# LED_Matrix.net
KiCad netlist of a schematic drawn in Altium Designer
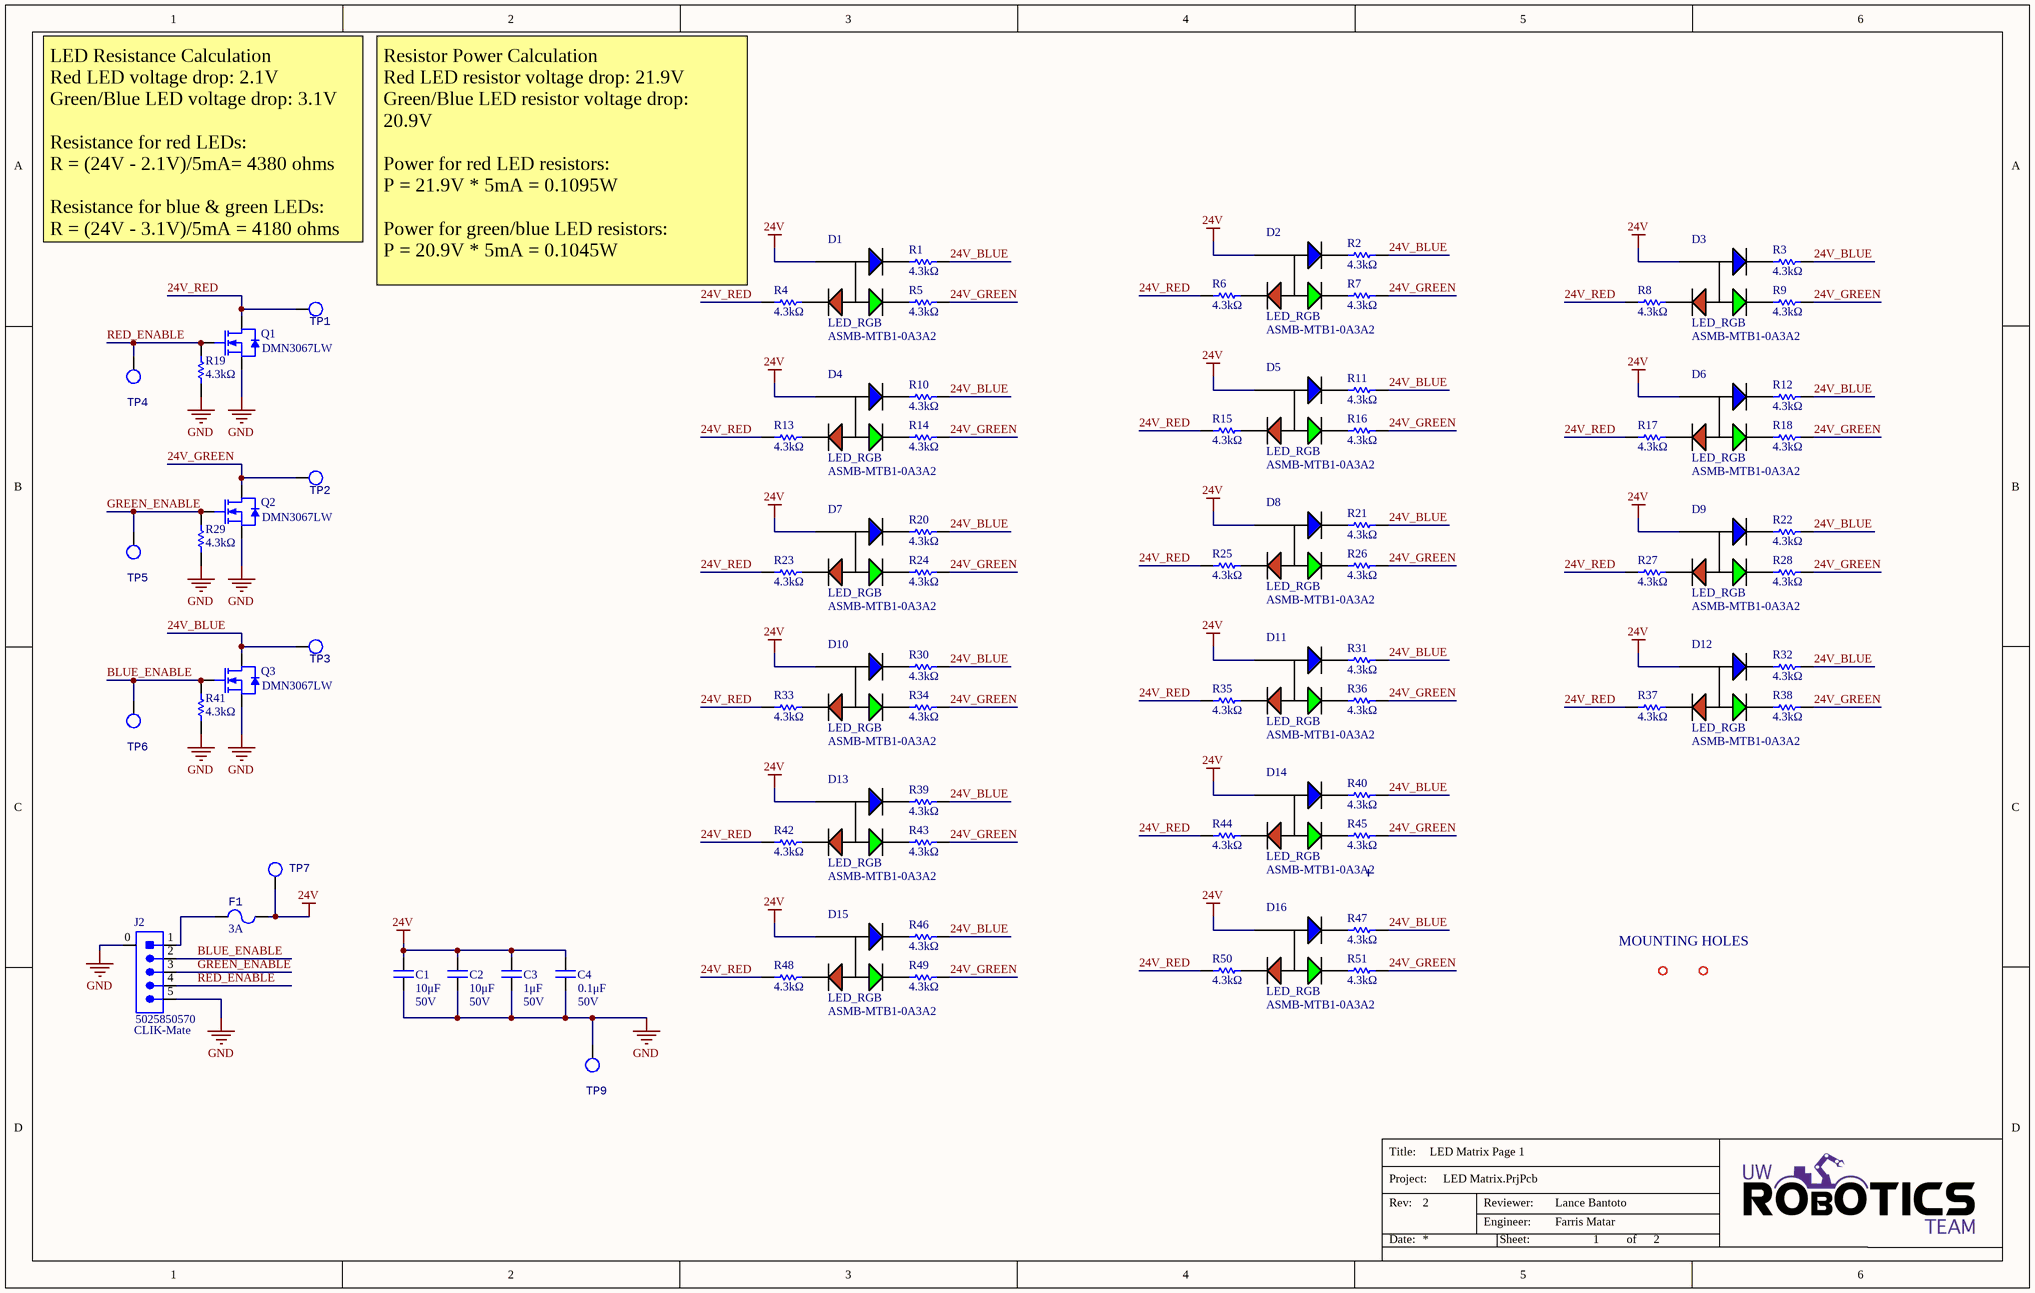
[diagram p0: LED Matrix.SchDoc]

(export (version "E")
  (design (tool "Eeschema 10.0.6"))
  (components
    (comp (ref "C1")
      (value "10μF")
      (footprint "CAP1210")
      (description "CAP CER 10UF 50V X7R 1210")
      (fields (field (name "VOLTAGE RATING") "50V") (field (name "Comment") "CAP_10uF_50V_1210"))
      (libsource (lib "UWRT_Schematic_Library_2020") (part "CAP_10uF_50V_1210"))
    )
    (comp (ref "C2")
      (value "10μF")
      (footprint "CAP1210")
      (description "CAP CER 10UF 50V X7R 1210")
      (fields (field (name "VOLTAGE RATING") "50V") (field (name "Comment") "CAP_10uF_50V_1210"))
      (libsource (lib "UWRT_Schematic_Library_2020") (part "CAP_10uF_50V_1210"))
    )
    (comp (ref "C3")
      (value "1μF")
      (footprint "CAP2012")
      (description "CAP CER 1UF 50V X7R 0805")
      (fields
        (field (name "VOLTAGE RATING") "50V")
        (field (name "LCSC PART #") "C28323")
        (field (name "Comment") "CAP_1uF_50V_0805")
      )
      (libsource (lib "UWRT_Schematic_Library_2020") (part "CAP_1uF_50V_0805"))
    )
    (comp (ref "C4")
      (value "0.1μF")
      (footprint "CAP2012")
      (description "CAP CER 0.1UF 50V X7R 0805")
      (fields
        (field (name "LCSC PART #") "C49678")
        (field (name "VOLTAGE RATING") "50V")
        (field (name "Comment") "CAP_0.1uF_50V_0805")
      )
      (libsource (lib "UWRT_Schematic_Library_2020") (part "CAP_0.1uF_50V_0805"))
    )
    (comp (ref "D1")
      (value "LED_RGB")
      (footprint "LED_RGB")
      (description "LED RGB DIFFUSED 4PLCC SMD")
      (fields (field (name "MANUFACTURER PART NUMBER 1") "ASMB-MTB1-0A3A2"))
      (libsource (lib "UWRT_Schematic_Library_2020") (part "LED_RGB"))
    )
    (comp (ref "D2")
      (value "LED_RGB")
      (footprint "LED_RGB")
      (description "LED RGB DIFFUSED 4PLCC SMD")
      (fields (field (name "MANUFACTURER PART NUMBER 1") "ASMB-MTB1-0A3A2"))
      (libsource (lib "UWRT_Schematic_Library_2020") (part "LED_RGB"))
    )
    (comp (ref "D3")
      (value "LED_RGB")
      (footprint "LED_RGB")
      (description "LED RGB DIFFUSED 4PLCC SMD")
      (fields (field (name "MANUFACTURER PART NUMBER 1") "ASMB-MTB1-0A3A2"))
      (libsource (lib "UWRT_Schematic_Library_2020") (part "LED_RGB"))
    )
    (comp (ref "D4")
      (value "LED_RGB")
      (footprint "LED_RGB")
      (description "LED RGB DIFFUSED 4PLCC SMD")
      (fields (field (name "MANUFACTURER PART NUMBER 1") "ASMB-MTB1-0A3A2"))
      (libsource (lib "UWRT_Schematic_Library_2020") (part "LED_RGB"))
    )
    (comp (ref "D5")
      (value "LED_RGB")
      (footprint "LED_RGB")
      (description "LED RGB DIFFUSED 4PLCC SMD")
      (fields (field (name "MANUFACTURER PART NUMBER 1") "ASMB-MTB1-0A3A2"))
      (libsource (lib "UWRT_Schematic_Library_2020") (part "LED_RGB"))
    )
    (comp (ref "D6")
      (value "LED_RGB")
      (footprint "LED_RGB")
      (description "LED RGB DIFFUSED 4PLCC SMD")
      (fields (field (name "MANUFACTURER PART NUMBER 1") "ASMB-MTB1-0A3A2"))
      (libsource (lib "UWRT_Schematic_Library_2020") (part "LED_RGB"))
    )
    (comp (ref "D7")
      (value "LED_RGB")
      (footprint "LED_RGB")
      (description "LED RGB DIFFUSED 4PLCC SMD")
      (fields (field (name "MANUFACTURER PART NUMBER 1") "ASMB-MTB1-0A3A2"))
      (libsource (lib "UWRT_Schematic_Library_2020") (part "LED_RGB"))
    )
    (comp (ref "D8")
      (value "LED_RGB")
      (footprint "LED_RGB")
      (description "LED RGB DIFFUSED 4PLCC SMD")
      (fields (field (name "MANUFACTURER PART NUMBER 1") "ASMB-MTB1-0A3A2"))
      (libsource (lib "UWRT_Schematic_Library_2020") (part "LED_RGB"))
    )
    (comp (ref "D9")
      (value "LED_RGB")
      (footprint "LED_RGB")
      (description "LED RGB DIFFUSED 4PLCC SMD")
      (fields (field (name "MANUFACTURER PART NUMBER 1") "ASMB-MTB1-0A3A2"))
      (libsource (lib "UWRT_Schematic_Library_2020") (part "LED_RGB"))
    )
    (comp (ref "D10")
      (value "LED_RGB")
      (footprint "LED_RGB")
      (description "LED RGB DIFFUSED 4PLCC SMD")
      (fields (field (name "MANUFACTURER PART NUMBER 1") "ASMB-MTB1-0A3A2"))
      (libsource (lib "UWRT_Schematic_Library_2020") (part "LED_RGB"))
    )
    (comp (ref "D11")
      (value "LED_RGB")
      (footprint "LED_RGB")
      (description "LED RGB DIFFUSED 4PLCC SMD")
      (fields (field (name "MANUFACTURER PART NUMBER 1") "ASMB-MTB1-0A3A2"))
      (libsource (lib "UWRT_Schematic_Library_2020") (part "LED_RGB"))
    )
    (comp (ref "D12")
      (value "LED_RGB")
      (footprint "LED_RGB")
      (description "LED RGB DIFFUSED 4PLCC SMD")
      (fields (field (name "MANUFACTURER PART NUMBER 1") "ASMB-MTB1-0A3A2"))
      (libsource (lib "UWRT_Schematic_Library_2020") (part "LED_RGB"))
    )
    (comp (ref "D13")
      (value "LED_RGB")
      (footprint "LED_RGB")
      (description "LED RGB DIFFUSED 4PLCC SMD")
      (fields (field (name "MANUFACTURER PART NUMBER 1") "ASMB-MTB1-0A3A2"))
      (libsource (lib "UWRT_Schematic_Library_2020") (part "LED_RGB"))
    )
    (comp (ref "D14")
      (value "LED_RGB")
      (footprint "LED_RGB")
      (description "LED RGB DIFFUSED 4PLCC SMD")
      (fields (field (name "MANUFACTURER PART NUMBER 1") "ASMB-MTB1-0A3A2"))
      (libsource (lib "UWRT_Schematic_Library_2020") (part "LED_RGB"))
    )
    (comp (ref "D15")
      (value "LED_RGB")
      (footprint "LED_RGB")
      (description "LED RGB DIFFUSED 4PLCC SMD")
      (fields (field (name "MANUFACTURER PART NUMBER 1") "ASMB-MTB1-0A3A2"))
      (libsource (lib "UWRT_Schematic_Library_2020") (part "LED_RGB"))
    )
    (comp (ref "D16")
      (value "LED_RGB")
      (footprint "LED_RGB")
      (description "LED RGB DIFFUSED 4PLCC SMD")
      (fields (field (name "MANUFACTURER PART NUMBER 1") "ASMB-MTB1-0A3A2"))
      (libsource (lib "UWRT_Schematic_Library_2020") (part "LED_RGB"))
    )
    (comp (ref "F1")
      (value "FUSE_3A_1206")
      (footprint "FUSE_1206")
      (description "FUSE BOARD MNT 3A 32VAC/VDC 1206")
      (fields (field (name "CURRENT RATING") "3A"))
      (libsource (lib "UWRT_Schematic_Library_2020") (part "FUSE_3A_1206"))
    )
    (comp (ref "J2")
      (value "CON_5M_SM_RA")
      (footprint "MOLEX-5025850570")
      (description "CONN HEADER SMD RIGHT ANGLE 1.5MM PITCH")
      (fields (field (name "MANUFACTURER PART NUMBER 1") "5025850570") (field (name "FAMILY") "CLIK-Mate"))
      (libsource (lib "UWRT_Schematic_Library_2020") (part "CON_5M_SM_RA"))
    )
    (comp (ref "MH1")
      (value "MOUNTING_HOLES")
      (footprint "MOUNTING_HOLE")
      (description "6cm x 6cm")
      (libsource (lib "UWRT_Schematic_Library_2020") (part "MOUNTING_HOLES"))
    )
    (comp (ref "MH2")
      (value "MOUNTING_HOLES")
      (footprint "MOUNTING_HOLE")
      (description "6cm x 6cm")
      (libsource (lib "UWRT_Schematic_Library_2020") (part "MOUNTING_HOLES"))
    )
    (comp (ref "Q1")
      (value "NMOS_30V_2.6A")
      (footprint "NMOS_SOT-323")
      (description "MOSFET N-CH 30V 2.6A SOT-323")
      (fields (field (name "MANUFACTURER PART NUMBER 1") "DMN3067LW"))
      (libsource (lib "UWRT_Schematic_Library_2020") (part "NMOS_30V_2.6A"))
    )
    (comp (ref "Q2")
      (value "NMOS_30V_2.6A")
      (footprint "NMOS_SOT-323")
      (description "MOSFET N-CH 30V 2.6A SOT-323")
      (fields (field (name "MANUFACTURER PART NUMBER 1") "DMN3067LW"))
      (libsource (lib "UWRT_Schematic_Library_2020") (part "NMOS_30V_2.6A"))
    )
    (comp (ref "Q3")
      (value "NMOS_30V_2.6A")
      (footprint "NMOS_SOT-323")
      (description "MOSFET N-CH 30V 2.6A SOT-323")
      (fields (field (name "MANUFACTURER PART NUMBER 1") "DMN3067LW"))
      (libsource (lib "UWRT_Schematic_Library_2020") (part "NMOS_30V_2.6A"))
    )
    (comp (ref "R1")
      (value "RES_4.3kΩ_1210_5%")
      (footprint "RES1210")
      (description "RES 4.3K OHM 5% 1/2W 1210")
      (fields (field (name "RESISTANCE") "4.3kΩ") (field (name "TOLERANCE") "5%"))
      (libsource (lib "UWRT_Schematic_Library_2020") (part "RES_4.3kΩ_1210_5%"))
    )
    (comp (ref "R2")
      (value "RES_4.3kΩ_1210_5%")
      (footprint "RES1210")
      (description "RES 4.3K OHM 5% 1/2W 1210")
      (fields (field (name "RESISTANCE") "4.3kΩ") (field (name "TOLERANCE") "5%"))
      (libsource (lib "UWRT_Schematic_Library_2020") (part "RES_4.3kΩ_1210_5%"))
    )
    (comp (ref "R3")
      (value "RES_4.3kΩ_1210_5%")
      (footprint "RES1210")
      (description "RES 4.3K OHM 5% 1/2W 1210")
      (fields (field (name "RESISTANCE") "4.3kΩ") (field (name "TOLERANCE") "5%"))
      (libsource (lib "UWRT_Schematic_Library_2020") (part "RES_4.3kΩ_1210_5%"))
    )
    (comp (ref "R4")
      (value "RES_4.3kΩ_1210_5%")
      (footprint "RES1210")
      (description "RES 4.3K OHM 5% 1/2W 1210")
      (fields (field (name "RESISTANCE") "4.3kΩ") (field (name "TOLERANCE") "5%"))
      (libsource (lib "UWRT_Schematic_Library_2020") (part "RES_4.3kΩ_1210_5%"))
    )
    (comp (ref "R5")
      (value "RES_4.3kΩ_1210_5%")
      (footprint "RES1210")
      (description "RES 4.3K OHM 5% 1/2W 1210")
      (fields (field (name "RESISTANCE") "4.3kΩ") (field (name "TOLERANCE") "5%"))
      (libsource (lib "UWRT_Schematic_Library_2020") (part "RES_4.3kΩ_1210_5%"))
    )
    (comp (ref "R6")
      (value "RES_4.3kΩ_1210_5%")
      (footprint "RES1210")
      (description "RES 4.3K OHM 5% 1/2W 1210")
      (fields (field (name "RESISTANCE") "4.3kΩ") (field (name "TOLERANCE") "5%"))
      (libsource (lib "UWRT_Schematic_Library_2020") (part "RES_4.3kΩ_1210_5%"))
    )
    (comp (ref "R7")
      (value "RES_4.3kΩ_1210_5%")
      (footprint "RES1210")
      (description "RES 4.3K OHM 5% 1/2W 1210")
      (fields (field (name "RESISTANCE") "4.3kΩ") (field (name "TOLERANCE") "5%"))
      (libsource (lib "UWRT_Schematic_Library_2020") (part "RES_4.3kΩ_1210_5%"))
    )
    (comp (ref "R8")
      (value "RES_4.3kΩ_1210_5%")
      (footprint "RES1210")
      (description "RES 4.3K OHM 5% 1/2W 1210")
      (fields (field (name "RESISTANCE") "4.3kΩ") (field (name "TOLERANCE") "5%"))
      (libsource (lib "UWRT_Schematic_Library_2020") (part "RES_4.3kΩ_1210_5%"))
    )
    (comp (ref "R9")
      (value "RES_4.3kΩ_1210_5%")
      (footprint "RES1210")
      (description "RES 4.3K OHM 5% 1/2W 1210")
      (fields (field (name "RESISTANCE") "4.3kΩ") (field (name "TOLERANCE") "5%"))
      (libsource (lib "UWRT_Schematic_Library_2020") (part "RES_4.3kΩ_1210_5%"))
    )
    (comp (ref "R10")
      (value "RES_4.3kΩ_1210_5%")
      (footprint "RES1210")
      (description "RES 4.3K OHM 5% 1/2W 1210")
      (fields (field (name "RESISTANCE") "4.3kΩ") (field (name "TOLERANCE") "5%"))
      (libsource (lib "UWRT_Schematic_Library_2020") (part "RES_4.3kΩ_1210_5%"))
    )
    (comp (ref "R11")
      (value "RES_4.3kΩ_1210_5%")
      (footprint "RES1210")
      (description "RES 4.3K OHM 5% 1/2W 1210")
      (fields (field (name "RESISTANCE") "4.3kΩ") (field (name "TOLERANCE") "5%"))
      (libsource (lib "UWRT_Schematic_Library_2020") (part "RES_4.3kΩ_1210_5%"))
    )
    (comp (ref "R12")
      (value "RES_4.3kΩ_1210_5%")
      (footprint "RES1210")
      (description "RES 4.3K OHM 5% 1/2W 1210")
      (fields (field (name "RESISTANCE") "4.3kΩ") (field (name "TOLERANCE") "5%"))
      (libsource (lib "UWRT_Schematic_Library_2020") (part "RES_4.3kΩ_1210_5%"))
    )
    (comp (ref "R13")
      (value "RES_4.3kΩ_1210_5%")
      (footprint "RES1210")
      (description "RES 4.3K OHM 5% 1/2W 1210")
      (fields (field (name "RESISTANCE") "4.3kΩ") (field (name "TOLERANCE") "5%"))
      (libsource (lib "UWRT_Schematic_Library_2020") (part "RES_4.3kΩ_1210_5%"))
    )
    (comp (ref "R14")
      (value "RES_4.3kΩ_1210_5%")
      (footprint "RES1210")
      (description "RES 4.3K OHM 5% 1/2W 1210")
      (fields (field (name "RESISTANCE") "4.3kΩ") (field (name "TOLERANCE") "5%"))
      (libsource (lib "UWRT_Schematic_Library_2020") (part "RES_4.3kΩ_1210_5%"))
    )
    (comp (ref "R15")
      (value "RES_4.3kΩ_1210_5%")
      (footprint "RES1210")
      (description "RES 4.3K OHM 5% 1/2W 1210")
      (fields (field (name "RESISTANCE") "4.3kΩ") (field (name "TOLERANCE") "5%"))
      (libsource (lib "UWRT_Schematic_Library_2020") (part "RES_4.3kΩ_1210_5%"))
    )
    (comp (ref "R16")
      (value "RES_4.3kΩ_1210_5%")
      (footprint "RES1210")
      (description "RES 4.3K OHM 5% 1/2W 1210")
      (fields (field (name "RESISTANCE") "4.3kΩ") (field (name "TOLERANCE") "5%"))
      (libsource (lib "UWRT_Schematic_Library_2020") (part "RES_4.3kΩ_1210_5%"))
    )
    (comp (ref "R17")
      (value "RES_4.3kΩ_1210_5%")
      (footprint "RES1210")
      (description "RES 4.3K OHM 5% 1/2W 1210")
      (fields (field (name "RESISTANCE") "4.3kΩ") (field (name "TOLERANCE") "5%"))
      (libsource (lib "UWRT_Schematic_Library_2020") (part "RES_4.3kΩ_1210_5%"))
    )
    (comp (ref "R18")
      (value "RES_4.3kΩ_1210_5%")
      (footprint "RES1210")
      (description "RES 4.3K OHM 5% 1/2W 1210")
      (fields (field (name "RESISTANCE") "4.3kΩ") (field (name "TOLERANCE") "5%"))
      (libsource (lib "UWRT_Schematic_Library_2020") (part "RES_4.3kΩ_1210_5%"))
    )
    (comp (ref "R19")
      (value "RES_4.3kΩ_1210_5%")
      (footprint "RES1210")
      (description "RES 4.3K OHM 5% 1/2W 1210")
      (fields (field (name "RESISTANCE") "4.3kΩ") (field (name "TOLERANCE") "5%"))
      (libsource (lib "UWRT_Schematic_Library_2020") (part "RES_4.3kΩ_1210_5%"))
    )
    (comp (ref "R20")
      (value "RES_4.3kΩ_1210_5%")
      (footprint "RES1210")
      (description "RES 4.3K OHM 5% 1/2W 1210")
      (fields (field (name "RESISTANCE") "4.3kΩ") (field (name "TOLERANCE") "5%"))
      (libsource (lib "UWRT_Schematic_Library_2020") (part "RES_4.3kΩ_1210_5%"))
    )
    (comp (ref "R21")
      (value "RES_4.3kΩ_1210_5%")
      (footprint "RES1210")
      (description "RES 4.3K OHM 5% 1/2W 1210")
      (fields (field (name "RESISTANCE") "4.3kΩ") (field (name "TOLERANCE") "5%"))
      (libsource (lib "UWRT_Schematic_Library_2020") (part "RES_4.3kΩ_1210_5%"))
    )
    (comp (ref "R22")
      (value "RES_4.3kΩ_1210_5%")
      (footprint "RES1210")
      (description "RES 4.3K OHM 5% 1/2W 1210")
      (fields (field (name "RESISTANCE") "4.3kΩ") (field (name "TOLERANCE") "5%"))
      (libsource (lib "UWRT_Schematic_Library_2020") (part "RES_4.3kΩ_1210_5%"))
    )
    (comp (ref "R23")
      (value "RES_4.3kΩ_1210_5%")
      (footprint "RES1210")
      (description "RES 4.3K OHM 5% 1/2W 1210")
      (fields (field (name "RESISTANCE") "4.3kΩ") (field (name "TOLERANCE") "5%"))
      (libsource (lib "UWRT_Schematic_Library_2020") (part "RES_4.3kΩ_1210_5%"))
    )
    (comp (ref "R24")
      (value "RES_4.3kΩ_1210_5%")
      (footprint "RES1210")
      (description "RES 4.3K OHM 5% 1/2W 1210")
      (fields (field (name "RESISTANCE") "4.3kΩ") (field (name "TOLERANCE") "5%"))
      (libsource (lib "UWRT_Schematic_Library_2020") (part "RES_4.3kΩ_1210_5%"))
    )
    (comp (ref "R25")
      (value "RES_4.3kΩ_1210_5%")
      (footprint "RES1210")
      (description "RES 4.3K OHM 5% 1/2W 1210")
      (fields (field (name "RESISTANCE") "4.3kΩ") (field (name "TOLERANCE") "5%"))
      (libsource (lib "UWRT_Schematic_Library_2020") (part "RES_4.3kΩ_1210_5%"))
    )
    (comp (ref "R26")
      (value "RES_4.3kΩ_1210_5%")
      (footprint "RES1210")
      (description "RES 4.3K OHM 5% 1/2W 1210")
      (fields (field (name "RESISTANCE") "4.3kΩ") (field (name "TOLERANCE") "5%"))
      (libsource (lib "UWRT_Schematic_Library_2020") (part "RES_4.3kΩ_1210_5%"))
    )
    (comp (ref "R27")
      (value "RES_4.3kΩ_1210_5%")
      (footprint "RES1210")
      (description "RES 4.3K OHM 5% 1/2W 1210")
      (fields (field (name "RESISTANCE") "4.3kΩ") (field (name "TOLERANCE") "5%"))
      (libsource (lib "UWRT_Schematic_Library_2020") (part "RES_4.3kΩ_1210_5%"))
    )
    (comp (ref "R28")
      (value "RES_4.3kΩ_1210_5%")
      (footprint "RES1210")
      (description "RES 4.3K OHM 5% 1/2W 1210")
      (fields (field (name "RESISTANCE") "4.3kΩ") (field (name "TOLERANCE") "5%"))
      (libsource (lib "UWRT_Schematic_Library_2020") (part "RES_4.3kΩ_1210_5%"))
    )
    (comp (ref "R29")
      (value "RES_4.3kΩ_1210_5%")
      (footprint "RES1210")
      (description "RES 4.3K OHM 5% 1/2W 1210")
      (fields (field (name "RESISTANCE") "4.3kΩ") (field (name "TOLERANCE") "5%"))
      (libsource (lib "UWRT_Schematic_Library_2020") (part "RES_4.3kΩ_1210_5%"))
    )
    (comp (ref "R30")
      (value "RES_4.3kΩ_1210_5%")
      (footprint "RES1210")
      (description "RES 4.3K OHM 5% 1/2W 1210")
      (fields (field (name "RESISTANCE") "4.3kΩ") (field (name "TOLERANCE") "5%"))
      (libsource (lib "UWRT_Schematic_Library_2020") (part "RES_4.3kΩ_1210_5%"))
    )
    (comp (ref "R31")
      (value "RES_4.3kΩ_1210_5%")
      (footprint "RES1210")
      (description "RES 4.3K OHM 5% 1/2W 1210")
      (fields (field (name "RESISTANCE") "4.3kΩ") (field (name "TOLERANCE") "5%"))
      (libsource (lib "UWRT_Schematic_Library_2020") (part "RES_4.3kΩ_1210_5%"))
    )
    (comp (ref "R32")
      (value "RES_4.3kΩ_1210_5%")
      (footprint "RES1210")
      (description "RES 4.3K OHM 5% 1/2W 1210")
      (fields (field (name "RESISTANCE") "4.3kΩ") (field (name "TOLERANCE") "5%"))
      (libsource (lib "UWRT_Schematic_Library_2020") (part "RES_4.3kΩ_1210_5%"))
    )
    (comp (ref "R33")
      (value "RES_4.3kΩ_1210_5%")
      (footprint "RES1210")
      (description "RES 4.3K OHM 5% 1/2W 1210")
      (fields (field (name "RESISTANCE") "4.3kΩ") (field (name "TOLERANCE") "5%"))
      (libsource (lib "UWRT_Schematic_Library_2020") (part "RES_4.3kΩ_1210_5%"))
    )
    (comp (ref "R34")
      (value "RES_4.3kΩ_1210_5%")
      (footprint "RES1210")
      (description "RES 4.3K OHM 5% 1/2W 1210")
      (fields (field (name "RESISTANCE") "4.3kΩ") (field (name "TOLERANCE") "5%"))
      (libsource (lib "UWRT_Schematic_Library_2020") (part "RES_4.3kΩ_1210_5%"))
    )
    (comp (ref "R35")
      (value "RES_4.3kΩ_1210_5%")
      (footprint "RES1210")
      (description "RES 4.3K OHM 5% 1/2W 1210")
      (fields (field (name "RESISTANCE") "4.3kΩ") (field (name "TOLERANCE") "5%"))
      (libsource (lib "UWRT_Schematic_Library_2020") (part "RES_4.3kΩ_1210_5%"))
    )
    (comp (ref "R36")
      (value "RES_4.3kΩ_1210_5%")
      (footprint "RES1210")
      (description "RES 4.3K OHM 5% 1/2W 1210")
      (fields (field (name "RESISTANCE") "4.3kΩ") (field (name "TOLERANCE") "5%"))
      (libsource (lib "UWRT_Schematic_Library_2020") (part "RES_4.3kΩ_1210_5%"))
    )
    (comp (ref "R37")
      (value "RES_4.3kΩ_1210_5%")
      (footprint "RES1210")
      (description "RES 4.3K OHM 5% 1/2W 1210")
      (fields (field (name "RESISTANCE") "4.3kΩ") (field (name "TOLERANCE") "5%"))
      (libsource (lib "UWRT_Schematic_Library_2020") (part "RES_4.3kΩ_1210_5%"))
    )
    (comp (ref "R38")
      (value "RES_4.3kΩ_1210_5%")
      (footprint "RES1210")
      (description "RES 4.3K OHM 5% 1/2W 1210")
      (fields (field (name "RESISTANCE") "4.3kΩ") (field (name "TOLERANCE") "5%"))
      (libsource (lib "UWRT_Schematic_Library_2020") (part "RES_4.3kΩ_1210_5%"))
    )
    (comp (ref "R39")
      (value "RES_4.3kΩ_1210_5%")
      (footprint "RES1210")
      (description "RES 4.3K OHM 5% 1/2W 1210")
      (fields (field (name "RESISTANCE") "4.3kΩ") (field (name "TOLERANCE") "5%"))
      (libsource (lib "UWRT_Schematic_Library_2020") (part "RES_4.3kΩ_1210_5%"))
    )
    (comp (ref "R40")
      (value "RES_4.3kΩ_1210_5%")
      (footprint "RES1210")
      (description "RES 4.3K OHM 5% 1/2W 1210")
      (fields (field (name "RESISTANCE") "4.3kΩ") (field (name "TOLERANCE") "5%"))
      (libsource (lib "UWRT_Schematic_Library_2020") (part "RES_4.3kΩ_1210_5%"))
    )
    (comp (ref "R41")
      (value "RES_4.3kΩ_1210_5%")
      (footprint "RES1210")
      (description "RES 4.3K OHM 5% 1/2W 1210")
      (fields (field (name "RESISTANCE") "4.3kΩ") (field (name "TOLERANCE") "5%"))
      (libsource (lib "UWRT_Schematic_Library_2020") (part "RES_4.3kΩ_1210_5%"))
    )
    (comp (ref "R42")
      (value "RES_4.3kΩ_1210_5%")
      (footprint "RES1210")
      (description "RES 4.3K OHM 5% 1/2W 1210")
      (fields (field (name "RESISTANCE") "4.3kΩ") (field (name "TOLERANCE") "5%"))
      (libsource (lib "UWRT_Schematic_Library_2020") (part "RES_4.3kΩ_1210_5%"))
    )
    (comp (ref "R43")
      (value "RES_4.3kΩ_1210_5%")
      (footprint "RES1210")
      (description "RES 4.3K OHM 5% 1/2W 1210")
      (fields (field (name "RESISTANCE") "4.3kΩ") (field (name "TOLERANCE") "5%"))
      (libsource (lib "UWRT_Schematic_Library_2020") (part "RES_4.3kΩ_1210_5%"))
    )
    (comp (ref "R44")
      (value "RES_4.3kΩ_1210_5%")
      (footprint "RES1210")
      (description "RES 4.3K OHM 5% 1/2W 1210")
      (fields (field (name "RESISTANCE") "4.3kΩ") (field (name "TOLERANCE") "5%"))
      (libsource (lib "UWRT_Schematic_Library_2020") (part "RES_4.3kΩ_1210_5%"))
    )
    (comp (ref "R45")
      (value "RES_4.3kΩ_1210_5%")
      (footprint "RES1210")
      (description "RES 4.3K OHM 5% 1/2W 1210")
      (fields (field (name "RESISTANCE") "4.3kΩ") (field (name "TOLERANCE") "5%"))
      (libsource (lib "UWRT_Schematic_Library_2020") (part "RES_4.3kΩ_1210_5%"))
    )
    (comp (ref "R46")
      (value "RES_4.3kΩ_1210_5%")
      (footprint "RES1210")
      (description "RES 4.3K OHM 5% 1/2W 1210")
      (fields (field (name "RESISTANCE") "4.3kΩ") (field (name "TOLERANCE") "5%"))
      (libsource (lib "UWRT_Schematic_Library_2020") (part "RES_4.3kΩ_1210_5%"))
    )
    (comp (ref "R47")
      (value "RES_4.3kΩ_1210_5%")
      (footprint "RES1210")
      (description "RES 4.3K OHM 5% 1/2W 1210")
      (fields (field (name "RESISTANCE") "4.3kΩ") (field (name "TOLERANCE") "5%"))
      (libsource (lib "UWRT_Schematic_Library_2020") (part "RES_4.3kΩ_1210_5%"))
    )
    (comp (ref "R48")
      (value "RES_4.3kΩ_1210_5%")
      (footprint "RES1210")
      (description "RES 4.3K OHM 5% 1/2W 1210")
      (fields (field (name "RESISTANCE") "4.3kΩ") (field (name "TOLERANCE") "5%"))
      (libsource (lib "UWRT_Schematic_Library_2020") (part "RES_4.3kΩ_1210_5%"))
    )
    (comp (ref "R49")
      (value "RES_4.3kΩ_1210_5%")
      (footprint "RES1210")
      (description "RES 4.3K OHM 5% 1/2W 1210")
      (fields (field (name "RESISTANCE") "4.3kΩ") (field (name "TOLERANCE") "5%"))
      (libsource (lib "UWRT_Schematic_Library_2020") (part "RES_4.3kΩ_1210_5%"))
    )
    (comp (ref "R50")
      (value "RES_4.3kΩ_1210_5%")
      (footprint "RES1210")
      (description "RES 4.3K OHM 5% 1/2W 1210")
      (fields (field (name "RESISTANCE") "4.3kΩ") (field (name "TOLERANCE") "5%"))
      (libsource (lib "UWRT_Schematic_Library_2020") (part "RES_4.3kΩ_1210_5%"))
    )
    (comp (ref "R51")
      (value "RES_4.3kΩ_1210_5%")
      (footprint "RES1210")
      (description "RES 4.3K OHM 5% 1/2W 1210")
      (fields (field (name "RESISTANCE") "4.3kΩ") (field (name "TOLERANCE") "5%"))
      (libsource (lib "UWRT_Schematic_Library_2020") (part "RES_4.3kΩ_1210_5%"))
    )
    (comp (ref "TP1")
      (value "TESTPOINT_LOOP")
      (footprint "TESTPOINT_LOOP")
      (description "TESTPOINT THRUHOLE")
      (libsource (lib "UWRT_Schematic_Library_2020") (part "TESTPOINT_LOOP"))
    )
    (comp (ref "TP2")
      (value "TESTPOINT_LOOP")
      (footprint "TESTPOINT_LOOP")
      (description "TESTPOINT THRUHOLE")
      (libsource (lib "UWRT_Schematic_Library_2020") (part "TESTPOINT_LOOP"))
    )
    (comp (ref "TP3")
      (value "TESTPOINT_LOOP")
      (footprint "TESTPOINT_LOOP")
      (description "TESTPOINT THRUHOLE")
      (libsource (lib "UWRT_Schematic_Library_2020") (part "TESTPOINT_LOOP"))
    )
    (comp (ref "TP4")
      (value "TESTPOINT_LOOP")
      (footprint "TESTPOINT_LOOP")
      (description "TESTPOINT THRUHOLE")
      (libsource (lib "UWRT_Schematic_Library_2020") (part "TESTPOINT_LOOP"))
    )
    (comp (ref "TP5")
      (value "TESTPOINT_LOOP")
      (footprint "TESTPOINT_LOOP")
      (description "TESTPOINT THRUHOLE")
      (libsource (lib "UWRT_Schematic_Library_2020") (part "TESTPOINT_LOOP"))
    )
    (comp (ref "TP6")
      (value "TESTPOINT_LOOP")
      (footprint "TESTPOINT_LOOP")
      (description "TESTPOINT THRUHOLE")
      (libsource (lib "UWRT_Schematic_Library_2020") (part "TESTPOINT_LOOP"))
    )
    (comp (ref "TP7")
      (value "TESTPOINT_LOOP")
      (footprint "TESTPOINT_LOOP")
      (description "TESTPOINT THRUHOLE")
      (libsource (lib "UWRT_Schematic_Library_2020") (part "TESTPOINT_LOOP"))
    )
    (comp (ref "TP9")
      (value "TESTPOINT_LOOP")
      (footprint "TESTPOINT_LOOP")
      (description "TESTPOINT THRUHOLE")
      (libsource (lib "UWRT_Schematic_Library_2020") (part "TESTPOINT_LOOP"))
    )
  )
  (nets
    (net (code "1") (name "/24V_BLUE") (class "Default")
      (node (ref "Q3") (pin "3") (pinfunction "DRAIN_3") (pintype "passive"))
      (node (ref "R1") (pin "2") (pinfunction "2_2") (pintype "passive"))
      (node (ref "R10") (pin "2") (pinfunction "2_2") (pintype "passive"))
      (node (ref "R11") (pin "2") (pinfunction "2_2") (pintype "passive"))
      (node (ref "R12") (pin "2") (pinfunction "2_2") (pintype "passive"))
      (node (ref "R2") (pin "2") (pinfunction "2_2") (pintype "passive"))
      (node (ref "R20") (pin "1") (pinfunction "1_1") (pintype "passive"))
      (node (ref "R21") (pin "1") (pinfunction "1_1") (pintype "passive"))
      (node (ref "R22") (pin "1") (pinfunction "1_1") (pintype "passive"))
      (node (ref "R3") (pin "2") (pinfunction "2_2") (pintype "passive"))
      (node (ref "R30") (pin "2") (pinfunction "2_2") (pintype "passive"))
      (node (ref "R31") (pin "2") (pinfunction "2_2") (pintype "passive"))
      (node (ref "R32") (pin "2") (pinfunction "2_2") (pintype "passive"))
      (node (ref "R39") (pin "1") (pinfunction "1_1") (pintype "passive"))
      (node (ref "R40") (pin "2") (pinfunction "2_2") (pintype "passive"))
      (node (ref "R46") (pin "2") (pinfunction "2_2") (pintype "passive"))
      (node (ref "R47") (pin "2") (pinfunction "2_2") (pintype "passive"))
      (node (ref "TP3") (pin "1") (pintype "passive"))
    )
    (net (code "2") (name "/24V_GREEN") (class "Default")
      (node (ref "Q2") (pin "3") (pinfunction "DRAIN_3") (pintype "passive"))
      (node (ref "R14") (pin "2") (pinfunction "2_2") (pintype "passive"))
      (node (ref "R16") (pin "2") (pinfunction "2_2") (pintype "passive"))
      (node (ref "R18") (pin "2") (pinfunction "2_2") (pintype "passive"))
      (node (ref "R24") (pin "2") (pinfunction "2_2") (pintype "passive"))
      (node (ref "R26") (pin "2") (pinfunction "2_2") (pintype "passive"))
      (node (ref "R28") (pin "2") (pinfunction "2_2") (pintype "passive"))
      (node (ref "R34") (pin "2") (pinfunction "2_2") (pintype "passive"))
      (node (ref "R36") (pin "2") (pinfunction "2_2") (pintype "passive"))
      (node (ref "R38") (pin "2") (pinfunction "2_2") (pintype "passive"))
      (node (ref "R43") (pin "2") (pinfunction "2_2") (pintype "passive"))
      (node (ref "R45") (pin "2") (pinfunction "2_2") (pintype "passive"))
      (node (ref "R49") (pin "2") (pinfunction "2_2") (pintype "passive"))
      (node (ref "R5") (pin "2") (pinfunction "2_2") (pintype "passive"))
      (node (ref "R51") (pin "2") (pinfunction "2_2") (pintype "passive"))
      (node (ref "R7") (pin "2") (pinfunction "2_2") (pintype "passive"))
      (node (ref "R9") (pin "2") (pinfunction "2_2") (pintype "passive"))
      (node (ref "TP2") (pin "1") (pintype "passive"))
    )
    (net (code "3") (name "/24V_RED") (class "Default")
      (node (ref "Q1") (pin "3") (pinfunction "DRAIN_3") (pintype "passive"))
      (node (ref "R13") (pin "1") (pinfunction "1_1") (pintype "passive"))
      (node (ref "R15") (pin "1") (pinfunction "1_1") (pintype "passive"))
      (node (ref "R17") (pin "1") (pinfunction "1_1") (pintype "passive"))
      (node (ref "R23") (pin "2") (pinfunction "2_2") (pintype "passive"))
      (node (ref "R25") (pin "1") (pinfunction "1_1") (pintype "passive"))
      (node (ref "R27") (pin "1") (pinfunction "1_1") (pintype "passive"))
      (node (ref "R33") (pin "1") (pinfunction "1_1") (pintype "passive"))
      (node (ref "R35") (pin "1") (pinfunction "1_1") (pintype "passive"))
      (node (ref "R37") (pin "1") (pinfunction "1_1") (pintype "passive"))
      (node (ref "R4") (pin "1") (pinfunction "1_1") (pintype "passive"))
      (node (ref "R42") (pin "1") (pinfunction "1_1") (pintype "passive"))
      (node (ref "R44") (pin "1") (pinfunction "1_1") (pintype "passive"))
      (node (ref "R48") (pin "1") (pinfunction "1_1") (pintype "passive"))
      (node (ref "R50") (pin "1") (pinfunction "1_1") (pintype "passive"))
      (node (ref "R6") (pin "1") (pinfunction "1_1") (pintype "passive"))
      (node (ref "R8") (pin "1") (pinfunction "1_1") (pintype "passive"))
      (node (ref "TP1") (pin "1") (pintype "passive"))
    )
    (net (code "4") (name "/BLUE_ENABLE") (class "Default")
      (node (ref "J2") (pin "2") (pinfunction "2_2") (pintype "passive"))
      (node (ref "Q3") (pin "1") (pinfunction "GATE_1") (pintype "passive"))
      (node (ref "R41") (pin "2") (pinfunction "2_2") (pintype "passive"))
      (node (ref "TP6") (pin "1") (pintype "passive"))
    )
    (net (code "5") (name "/GREEN_ENABLE") (class "Default")
      (node (ref "J2") (pin "3") (pinfunction "3_3") (pintype "passive"))
      (node (ref "Q2") (pin "1") (pinfunction "GATE_1") (pintype "passive"))
      (node (ref "R29") (pin "2") (pinfunction "2_2") (pintype "passive"))
      (node (ref "TP5") (pin "1") (pintype "passive"))
    )
    (net (code "6") (name "/RED_ENABLE") (class "Default")
      (node (ref "J2") (pin "4") (pinfunction "4_4") (pintype "passive"))
      (node (ref "Q1") (pin "1") (pinfunction "GATE_1") (pintype "passive"))
      (node (ref "R19") (pin "2") (pinfunction "2_2") (pintype "passive"))
      (node (ref "TP4") (pin "1") (pintype "passive"))
    )
    (net (code "7") (name "24V") (class "Default")
      (node (ref "C1") (pin "2") (pinfunction "2_2") (pintype "passive"))
      (node (ref "C2") (pin "2") (pinfunction "2_2") (pintype "passive"))
      (node (ref "C3") (pin "1") (pinfunction "1_1") (pintype "passive"))
      (node (ref "C4") (pin "2") (pinfunction "2_2") (pintype "passive"))
      (node (ref "D1") (pin "4") (pinfunction "COMMON_ANODE_4") (pintype "passive"))
      (node (ref "D10") (pin "4") (pinfunction "COMMON_ANODE_4") (pintype "passive"))
      (node (ref "D11") (pin "4") (pinfunction "COMMON_ANODE_4") (pintype "passive"))
      (node (ref "D12") (pin "4") (pinfunction "COMMON_ANODE_4") (pintype "passive"))
      (node (ref "D13") (pin "4") (pinfunction "COMMON_ANODE_4") (pintype "passive"))
      (node (ref "D14") (pin "4") (pinfunction "COMMON_ANODE_4") (pintype "passive"))
      (node (ref "D15") (pin "4") (pinfunction "COMMON_ANODE_4") (pintype "passive"))
      (node (ref "D16") (pin "4") (pinfunction "COMMON_ANODE_4") (pintype "passive"))
      (node (ref "D2") (pin "4") (pinfunction "COMMON_ANODE_4") (pintype "passive"))
      (node (ref "D3") (pin "4") (pinfunction "COMMON_ANODE_4") (pintype "passive"))
      (node (ref "D4") (pin "4") (pinfunction "COMMON_ANODE_4") (pintype "passive"))
      (node (ref "D5") (pin "4") (pinfunction "COMMON_ANODE_4") (pintype "passive"))
      (node (ref "D6") (pin "4") (pinfunction "COMMON_ANODE_4") (pintype "passive"))
      (node (ref "D7") (pin "4") (pinfunction "COMMON_ANODE_4") (pintype "passive"))
      (node (ref "D8") (pin "4") (pinfunction "COMMON_ANODE_4") (pintype "passive"))
      (node (ref "D9") (pin "4") (pinfunction "COMMON_ANODE_4") (pintype "passive"))
      (node (ref "F1") (pin "1") (pinfunction "1_1") (pintype "passive"))
      (node (ref "TP7") (pin "1") (pintype "passive"))
    )
    (net (code "8") (name "GND") (class "Default")
      (node (ref "C1") (pin "1") (pinfunction "1_1") (pintype "passive"))
      (node (ref "C2") (pin "1") (pinfunction "1_1") (pintype "passive"))
      (node (ref "C3") (pin "2") (pinfunction "2_2") (pintype "passive"))
      (node (ref "C4") (pin "1") (pinfunction "1_1") (pintype "passive"))
      (node (ref "J2") (pin "0") (pinfunction "0_0") (pintype "passive"))
      (node (ref "J2") (pin "5") (pinfunction "5_5") (pintype "passive"))
      (node (ref "Q1") (pin "2") (pinfunction "SOURCE_2") (pintype "passive"))
      (node (ref "Q2") (pin "2") (pinfunction "SOURCE_2") (pintype "passive"))
      (node (ref "Q3") (pin "2") (pinfunction "SOURCE_2") (pintype "passive"))
      (node (ref "R19") (pin "1") (pinfunction "1_1") (pintype "passive"))
      (node (ref "R29") (pin "1") (pinfunction "1_1") (pintype "passive"))
      (node (ref "R41") (pin "1") (pinfunction "1_1") (pintype "passive"))
      (node (ref "TP9") (pin "1") (pintype "passive"))
    )
    (net (code "9") (name "Net-(D1-CATHODE_(BLUE))") (class "Default")
      (node (ref "D1") (pin "3") (pinfunction "CATHODE_(BLUE)_3") (pintype "passive"))
      (node (ref "R1") (pin "1") (pinfunction "1_1") (pintype "passive"))
    )
    (net (code "10") (name "Net-(D1-CATHODE_(GREEN))") (class "Default")
      (node (ref "D1") (pin "2") (pinfunction "CATHODE_(GREEN)_2") (pintype "passive"))
      (node (ref "R5") (pin "1") (pinfunction "1_1") (pintype "passive"))
    )
    (net (code "11") (name "Net-(D1-CATHODE_(RED))") (class "Default")
      (node (ref "D1") (pin "1") (pinfunction "CATHODE_(RED)_1") (pintype "passive"))
      (node (ref "R4") (pin "2") (pinfunction "2_2") (pintype "passive"))
    )
    (net (code "12") (name "Net-(D2-CATHODE_(BLUE))") (class "Default")
      (node (ref "D2") (pin "3") (pinfunction "CATHODE_(BLUE)_3") (pintype "passive"))
      (node (ref "R2") (pin "1") (pinfunction "1_1") (pintype "passive"))
    )
    (net (code "13") (name "Net-(D2-CATHODE_(GREEN))") (class "Default")
      (node (ref "D2") (pin "2") (pinfunction "CATHODE_(GREEN)_2") (pintype "passive"))
      (node (ref "R7") (pin "1") (pinfunction "1_1") (pintype "passive"))
    )
    (net (code "14") (name "Net-(D2-CATHODE_(RED))") (class "Default")
      (node (ref "D2") (pin "1") (pinfunction "CATHODE_(RED)_1") (pintype "passive"))
      (node (ref "R6") (pin "2") (pinfunction "2_2") (pintype "passive"))
    )
    (net (code "15") (name "Net-(D3-CATHODE_(BLUE))") (class "Default")
      (node (ref "D3") (pin "3") (pinfunction "CATHODE_(BLUE)_3") (pintype "passive"))
      (node (ref "R3") (pin "1") (pinfunction "1_1") (pintype "passive"))
    )
    (net (code "16") (name "Net-(D3-CATHODE_(GREEN))") (class "Default")
      (node (ref "D3") (pin "2") (pinfunction "CATHODE_(GREEN)_2") (pintype "passive"))
      (node (ref "R9") (pin "1") (pinfunction "1_1") (pintype "passive"))
    )
    (net (code "17") (name "Net-(D3-CATHODE_(RED))") (class "Default")
      (node (ref "D3") (pin "1") (pinfunction "CATHODE_(RED)_1") (pintype "passive"))
      (node (ref "R8") (pin "2") (pinfunction "2_2") (pintype "passive"))
    )
    (net (code "18") (name "Net-(D4-CATHODE_(BLUE))") (class "Default")
      (node (ref "D4") (pin "3") (pinfunction "CATHODE_(BLUE)_3") (pintype "passive"))
      (node (ref "R10") (pin "1") (pinfunction "1_1") (pintype "passive"))
    )
    (net (code "19") (name "Net-(D4-CATHODE_(GREEN))") (class "Default")
      (node (ref "D4") (pin "2") (pinfunction "CATHODE_(GREEN)_2") (pintype "passive"))
      (node (ref "R14") (pin "1") (pinfunction "1_1") (pintype "passive"))
    )
    (net (code "20") (name "Net-(D4-CATHODE_(RED))") (class "Default")
      (node (ref "D4") (pin "1") (pinfunction "CATHODE_(RED)_1") (pintype "passive"))
      (node (ref "R13") (pin "2") (pinfunction "2_2") (pintype "passive"))
    )
    (net (code "21") (name "Net-(D5-CATHODE_(BLUE))") (class "Default")
      (node (ref "D5") (pin "3") (pinfunction "CATHODE_(BLUE)_3") (pintype "passive"))
      (node (ref "R11") (pin "1") (pinfunction "1_1") (pintype "passive"))
    )
    (net (code "22") (name "Net-(D5-CATHODE_(GREEN))") (class "Default")
      (node (ref "D5") (pin "2") (pinfunction "CATHODE_(GREEN)_2") (pintype "passive"))
      (node (ref "R16") (pin "1") (pinfunction "1_1") (pintype "passive"))
    )
    (net (code "23") (name "Net-(D5-CATHODE_(RED))") (class "Default")
      (node (ref "D5") (pin "1") (pinfunction "CATHODE_(RED)_1") (pintype "passive"))
      (node (ref "R15") (pin "2") (pinfunction "2_2") (pintype "passive"))
    )
    (net (code "24") (name "Net-(D6-CATHODE_(BLUE))") (class "Default")
      (node (ref "D6") (pin "3") (pinfunction "CATHODE_(BLUE)_3") (pintype "passive"))
      (node (ref "R12") (pin "1") (pinfunction "1_1") (pintype "passive"))
    )
    (net (code "25") (name "Net-(D6-CATHODE_(GREEN))") (class "Default")
      (node (ref "D6") (pin "2") (pinfunction "CATHODE_(GREEN)_2") (pintype "passive"))
      (node (ref "R18") (pin "1") (pinfunction "1_1") (pintype "passive"))
    )
    (net (code "26") (name "Net-(D6-CATHODE_(RED))") (class "Default")
      (node (ref "D6") (pin "1") (pinfunction "CATHODE_(RED)_1") (pintype "passive"))
      (node (ref "R17") (pin "2") (pinfunction "2_2") (pintype "passive"))
    )
    (net (code "27") (name "Net-(D7-CATHODE_(BLUE))") (class "Default")
      (node (ref "D7") (pin "3") (pinfunction "CATHODE_(BLUE)_3") (pintype "passive"))
      (node (ref "R20") (pin "2") (pinfunction "2_2") (pintype "passive"))
    )
    (net (code "28") (name "Net-(D7-CATHODE_(GREEN))") (class "Default")
      (node (ref "D7") (pin "2") (pinfunction "CATHODE_(GREEN)_2") (pintype "passive"))
      (node (ref "R24") (pin "1") (pinfunction "1_1") (pintype "passive"))
    )
    (net (code "29") (name "Net-(D7-CATHODE_(RED))") (class "Default")
      (node (ref "D7") (pin "1") (pinfunction "CATHODE_(RED)_1") (pintype "passive"))
      (node (ref "R23") (pin "1") (pinfunction "1_1") (pintype "passive"))
    )
    (net (code "30") (name "Net-(D8-CATHODE_(BLUE))") (class "Default")
      (node (ref "D8") (pin "3") (pinfunction "CATHODE_(BLUE)_3") (pintype "passive"))
      (node (ref "R21") (pin "2") (pinfunction "2_2") (pintype "passive"))
    )
    (net (code "31") (name "Net-(D8-CATHODE_(GREEN))") (class "Default")
      (node (ref "D8") (pin "2") (pinfunction "CATHODE_(GREEN)_2") (pintype "passive"))
      (node (ref "R26") (pin "1") (pinfunction "1_1") (pintype "passive"))
    )
    (net (code "32") (name "Net-(D8-CATHODE_(RED))") (class "Default")
      (node (ref "D8") (pin "1") (pinfunction "CATHODE_(RED)_1") (pintype "passive"))
      (node (ref "R25") (pin "2") (pinfunction "2_2") (pintype "passive"))
    )
    (net (code "33") (name "Net-(D9-CATHODE_(BLUE))") (class "Default")
      (node (ref "D9") (pin "3") (pinfunction "CATHODE_(BLUE)_3") (pintype "passive"))
      (node (ref "R22") (pin "2") (pinfunction "2_2") (pintype "passive"))
    )
    (net (code "34") (name "Net-(D9-CATHODE_(GREEN))") (class "Default")
      (node (ref "D9") (pin "2") (pinfunction "CATHODE_(GREEN)_2") (pintype "passive"))
      (node (ref "R28") (pin "1") (pinfunction "1_1") (pintype "passive"))
    )
    (net (code "35") (name "Net-(D9-CATHODE_(RED))") (class "Default")
      (node (ref "D9") (pin "1") (pinfunction "CATHODE_(RED)_1") (pintype "passive"))
      (node (ref "R27") (pin "2") (pinfunction "2_2") (pintype "passive"))
    )
    (net (code "36") (name "Net-(D10-CATHODE_(BLUE))") (class "Default")
      (node (ref "D10") (pin "3") (pinfunction "CATHODE_(BLUE)_3") (pintype "passive"))
      (node (ref "R30") (pin "1") (pinfunction "1_1") (pintype "passive"))
    )
    (net (code "37") (name "Net-(D10-CATHODE_(GREEN))") (class "Default")
      (node (ref "D10") (pin "2") (pinfunction "CATHODE_(GREEN)_2") (pintype "passive"))
      (node (ref "R34") (pin "1") (pinfunction "1_1") (pintype "passive"))
    )
    (net (code "38") (name "Net-(D10-CATHODE_(RED))") (class "Default")
      (node (ref "D10") (pin "1") (pinfunction "CATHODE_(RED)_1") (pintype "passive"))
      (node (ref "R33") (pin "2") (pinfunction "2_2") (pintype "passive"))
    )
    (net (code "39") (name "Net-(D11-CATHODE_(BLUE))") (class "Default")
      (node (ref "D11") (pin "3") (pinfunction "CATHODE_(BLUE)_3") (pintype "passive"))
      (node (ref "R31") (pin "1") (pinfunction "1_1") (pintype "passive"))
    )
    (net (code "40") (name "Net-(D11-CATHODE_(GREEN))") (class "Default")
      (node (ref "D11") (pin "2") (pinfunction "CATHODE_(GREEN)_2") (pintype "passive"))
      (node (ref "R36") (pin "1") (pinfunction "1_1") (pintype "passive"))
    )
    (net (code "41") (name "Net-(D11-CATHODE_(RED))") (class "Default")
      (node (ref "D11") (pin "1") (pinfunction "CATHODE_(RED)_1") (pintype "passive"))
      (node (ref "R35") (pin "2") (pinfunction "2_2") (pintype "passive"))
    )
    (net (code "42") (name "Net-(D12-CATHODE_(BLUE))") (class "Default")
      (node (ref "D12") (pin "3") (pinfunction "CATHODE_(BLUE)_3") (pintype "passive"))
      (node (ref "R32") (pin "1") (pinfunction "1_1") (pintype "passive"))
    )
    (net (code "43") (name "Net-(D12-CATHODE_(GREEN))") (class "Default")
      (node (ref "D12") (pin "2") (pinfunction "CATHODE_(GREEN)_2") (pintype "passive"))
      (node (ref "R38") (pin "1") (pinfunction "1_1") (pintype "passive"))
    )
    (net (code "44") (name "Net-(D12-CATHODE_(RED))") (class "Default")
      (node (ref "D12") (pin "1") (pinfunction "CATHODE_(RED)_1") (pintype "passive"))
      (node (ref "R37") (pin "2") (pinfunction "2_2") (pintype "passive"))
    )
    (net (code "45") (name "Net-(D13-CATHODE_(BLUE))") (class "Default")
      (node (ref "D13") (pin "3") (pinfunction "CATHODE_(BLUE)_3") (pintype "passive"))
      (node (ref "R39") (pin "2") (pinfunction "2_2") (pintype "passive"))
    )
    (net (code "46") (name "Net-(D13-CATHODE_(GREEN))") (class "Default")
      (node (ref "D13") (pin "2") (pinfunction "CATHODE_(GREEN)_2") (pintype "passive"))
      (node (ref "R43") (pin "1") (pinfunction "1_1") (pintype "passive"))
    )
    (net (code "47") (name "Net-(D13-CATHODE_(RED))") (class "Default")
      (node (ref "D13") (pin "1") (pinfunction "CATHODE_(RED)_1") (pintype "passive"))
      (node (ref "R42") (pin "2") (pinfunction "2_2") (pintype "passive"))
    )
    (net (code "48") (name "Net-(D14-CATHODE_(BLUE))") (class "Default")
      (node (ref "D14") (pin "3") (pinfunction "CATHODE_(BLUE)_3") (pintype "passive"))
      (node (ref "R40") (pin "1") (pinfunction "1_1") (pintype "passive"))
    )
    (net (code "49") (name "Net-(D14-CATHODE_(GREEN))") (class "Default")
      (node (ref "D14") (pin "2") (pinfunction "CATHODE_(GREEN)_2") (pintype "passive"))
      (node (ref "R45") (pin "1") (pinfunction "1_1") (pintype "passive"))
    )
    (net (code "50") (name "Net-(D14-CATHODE_(RED))") (class "Default")
      (node (ref "D14") (pin "1") (pinfunction "CATHODE_(RED)_1") (pintype "passive"))
      (node (ref "R44") (pin "2") (pinfunction "2_2") (pintype "passive"))
    )
    (net (code "51") (name "Net-(D15-CATHODE_(BLUE))") (class "Default")
      (node (ref "D15") (pin "3") (pinfunction "CATHODE_(BLUE)_3") (pintype "passive"))
      (node (ref "R46") (pin "1") (pinfunction "1_1") (pintype "passive"))
    )
    (net (code "52") (name "Net-(D15-CATHODE_(GREEN))") (class "Default")
      (node (ref "D15") (pin "2") (pinfunction "CATHODE_(GREEN)_2") (pintype "passive"))
      (node (ref "R49") (pin "1") (pinfunction "1_1") (pintype "passive"))
    )
    (net (code "53") (name "Net-(D15-CATHODE_(RED))") (class "Default")
      (node (ref "D15") (pin "1") (pinfunction "CATHODE_(RED)_1") (pintype "passive"))
      (node (ref "R48") (pin "2") (pinfunction "2_2") (pintype "passive"))
    )
    (net (code "54") (name "Net-(D16-CATHODE_(BLUE))") (class "Default")
      (node (ref "D16") (pin "3") (pinfunction "CATHODE_(BLUE)_3") (pintype "passive"))
      (node (ref "R47") (pin "1") (pinfunction "1_1") (pintype "passive"))
    )
    (net (code "55") (name "Net-(D16-CATHODE_(GREEN))") (class "Default")
      (node (ref "D16") (pin "2") (pinfunction "CATHODE_(GREEN)_2") (pintype "passive"))
      (node (ref "R51") (pin "1") (pinfunction "1_1") (pintype "passive"))
    )
    (net (code "56") (name "Net-(D16-CATHODE_(RED))") (class "Default")
      (node (ref "D16") (pin "1") (pinfunction "CATHODE_(RED)_1") (pintype "passive"))
      (node (ref "R50") (pin "2") (pinfunction "2_2") (pintype "passive"))
    )
    (net (code "57") (name "Net-(F1-Pad2)") (class "Default")
      (node (ref "F1") (pin "2") (pinfunction "2_2") (pintype "passive"))
      (node (ref "J2") (pin "1") (pinfunction "1_1") (pintype "passive"))
    )
  )
)
